# MIC.net
KiCad netlist of a schematic drawn in Altium Designer
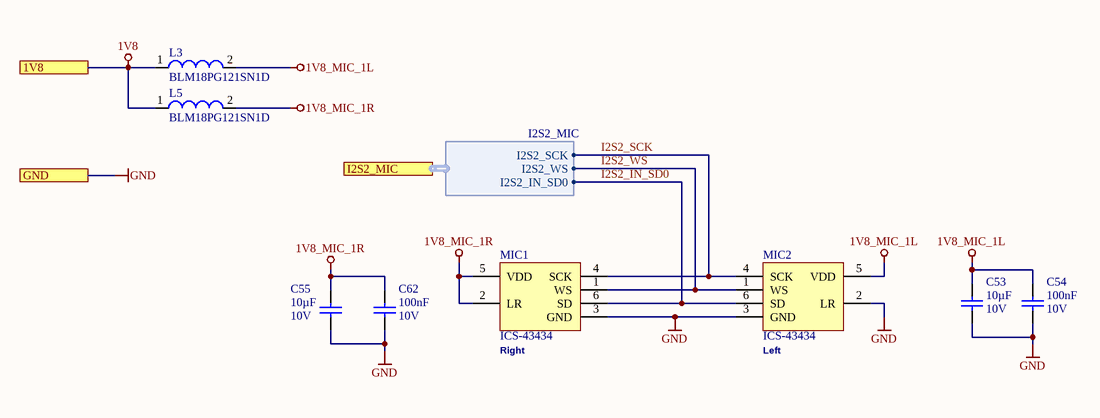
[diagram p0: MIC.SchDoc]

(export (version "E")
  (design (tool "Eeschema 10.0.6"))
  (components
    (comp (ref "C53")
      (value "10µF")
      (footprint "CAPC0603(1608)100_L")
      (description "CAP CER 10UF 10V X5R 0603 20%")
      (fields
        (field (name "TOLERANCE") "20%")
        (field (name "VOLTAGE RATING") "10V")
        (field (name "Comment") "GRM188R61A106ME69D")
      )
      (libsource (lib "Luxonis LLC") (part "LLL153C70G474ME17E"))
    )
    (comp (ref "C54")
      (value "100nF")
      (footprint "CAPC0402(1005)70_L")
      (description "CAP CER 0.1UF 10V X7R 0402 5%")
      (fields
        (field (name "TOLERANCE") "5%")
        (field (name "VOLTAGE RATING") "10V")
        (field (name "Comment") "GRM155R71A104JA01D")
      )
      (libsource (lib "Luxonis LLC") (part "GRM188R61C475KAAJD"))
    )
    (comp (ref "C55")
      (value "10µF")
      (footprint "CAPC0603(1608)100_L")
      (description "CAP CER 10UF 10V X5R 0603 20%")
      (fields
        (field (name "TOLERANCE") "20%")
        (field (name "VOLTAGE RATING") "10V")
        (field (name "Comment") "GRM188R61A106ME69D")
      )
      (libsource (lib "Luxonis LLC") (part "LLL153C70G474ME17E"))
    )
    (comp (ref "C62")
      (value "100nF")
      (footprint "CAPC0402(1005)70_L")
      (description "CAP CER 0.1UF 10V X7R 0402 5%")
      (fields
        (field (name "TOLERANCE") "5%")
        (field (name "VOLTAGE RATING") "10V")
        (field (name "Comment") "GRM155R71A104JA01D")
      )
      (libsource (lib "Luxonis LLC") (part "GRM188R61C475KAAJD"))
    )
    (comp (ref "L3")
      (value "BLM18PG121SN1D")
      (footprint "BLM18PG121SN1D_N")
      (description "FERRITE BEAD 120 OHM 0603 1LN")
      (fields (field (name "TOLERANCE") "25%"))
      (libsource (lib "Luxonis LLC") (part "IHLP1616BZERR22M01"))
    )
    (comp (ref "L5")
      (value "BLM18PG121SN1D")
      (footprint "BLM18PG121SN1D_N")
      (description "FERRITE BEAD 120 OHM 0603 1LN")
      (fields (field (name "TOLERANCE") "25%"))
      (libsource (lib "Luxonis LLC") (part "IHLP1616BZERR22M01"))
    )
    (comp (ref "MIC1")
      (value "ICS-43434")
      (footprint "ICS-43434")
      (libsource (lib "Luxonis LLC") (part "ICS-43434"))
    )
    (comp (ref "MIC2") (value "ICS-43434") (footprint "ICS-43434") (libsource (lib "") (part "ICS-43434_1")))
  )
  (nets
    (net (code "2") (name "/I2S2_IN_SD0") (class "Default")
      (node (ref "MIC1") (pin "6") (pinfunction "SD_6") (pintype "passive"))
      (node (ref "MIC2") (pin "6") (pinfunction "SD_6") (pintype "passive"))
    )
    (net (code "3") (name "/I2S2_SCK") (class "Default")
      (node (ref "MIC1") (pin "4") (pinfunction "SCK_4") (pintype "passive"))
      (node (ref "MIC2") (pin "4") (pinfunction "SCK_4") (pintype "passive"))
    )
    (net (code "4") (name "/I2S2_WS") (class "Default")
      (node (ref "MIC1") (pin "1") (pinfunction "WS_1") (pintype "passive"))
      (node (ref "MIC2") (pin "1") (pinfunction "WS_1") (pintype "passive"))
    )
    (net (code "6") (name "1V8") (class "Default")
      (node (ref "L3") (pin "1") (pinfunction "1_1") (pintype "passive"))
      (node (ref "L5") (pin "1") (pinfunction "1_1") (pintype "passive"))
    )
    (net (code "7") (name "1V8_MIC_1L") (class "Default")
      (node (ref "C53") (pin "2") (pinfunction "2_2") (pintype "passive"))
      (node (ref "C54") (pin "2") (pinfunction "2_2") (pintype "passive"))
      (node (ref "L3") (pin "2") (pinfunction "2_2") (pintype "passive"))
      (node (ref "MIC2") (pin "5") (pinfunction "VDD_5") (pintype "passive"))
    )
    (net (code "8") (name "1V8_MIC_1R") (class "Default")
      (node (ref "C55") (pin "2") (pinfunction "2_2") (pintype "passive"))
      (node (ref "C62") (pin "2") (pinfunction "2_2") (pintype "passive"))
      (node (ref "L5") (pin "2") (pinfunction "2_2") (pintype "passive"))
      (node (ref "MIC1") (pin "2") (pinfunction "LR_2") (pintype "passive"))
      (node (ref "MIC1") (pin "5") (pinfunction "VDD_5") (pintype "passive"))
    )
    (net (code "9") (name "GND") (class "Default")
      (node (ref "C53") (pin "1") (pinfunction "1_1") (pintype "passive"))
      (node (ref "C54") (pin "1") (pinfunction "1_1") (pintype "passive"))
      (node (ref "C55") (pin "1") (pinfunction "1_1") (pintype "passive"))
      (node (ref "C62") (pin "1") (pinfunction "1_1") (pintype "passive"))
      (node (ref "MIC1") (pin "3") (pinfunction "GND_3") (pintype "passive"))
      (node (ref "MIC2") (pin "2") (pinfunction "LR_2") (pintype "passive"))
      (node (ref "MIC2") (pin "3") (pinfunction "GND_3") (pintype "passive"))
    )
  )
)
